# SCH_GP40_keyboard.net
KiCad netlist of a schematic drawn in EasyEDA
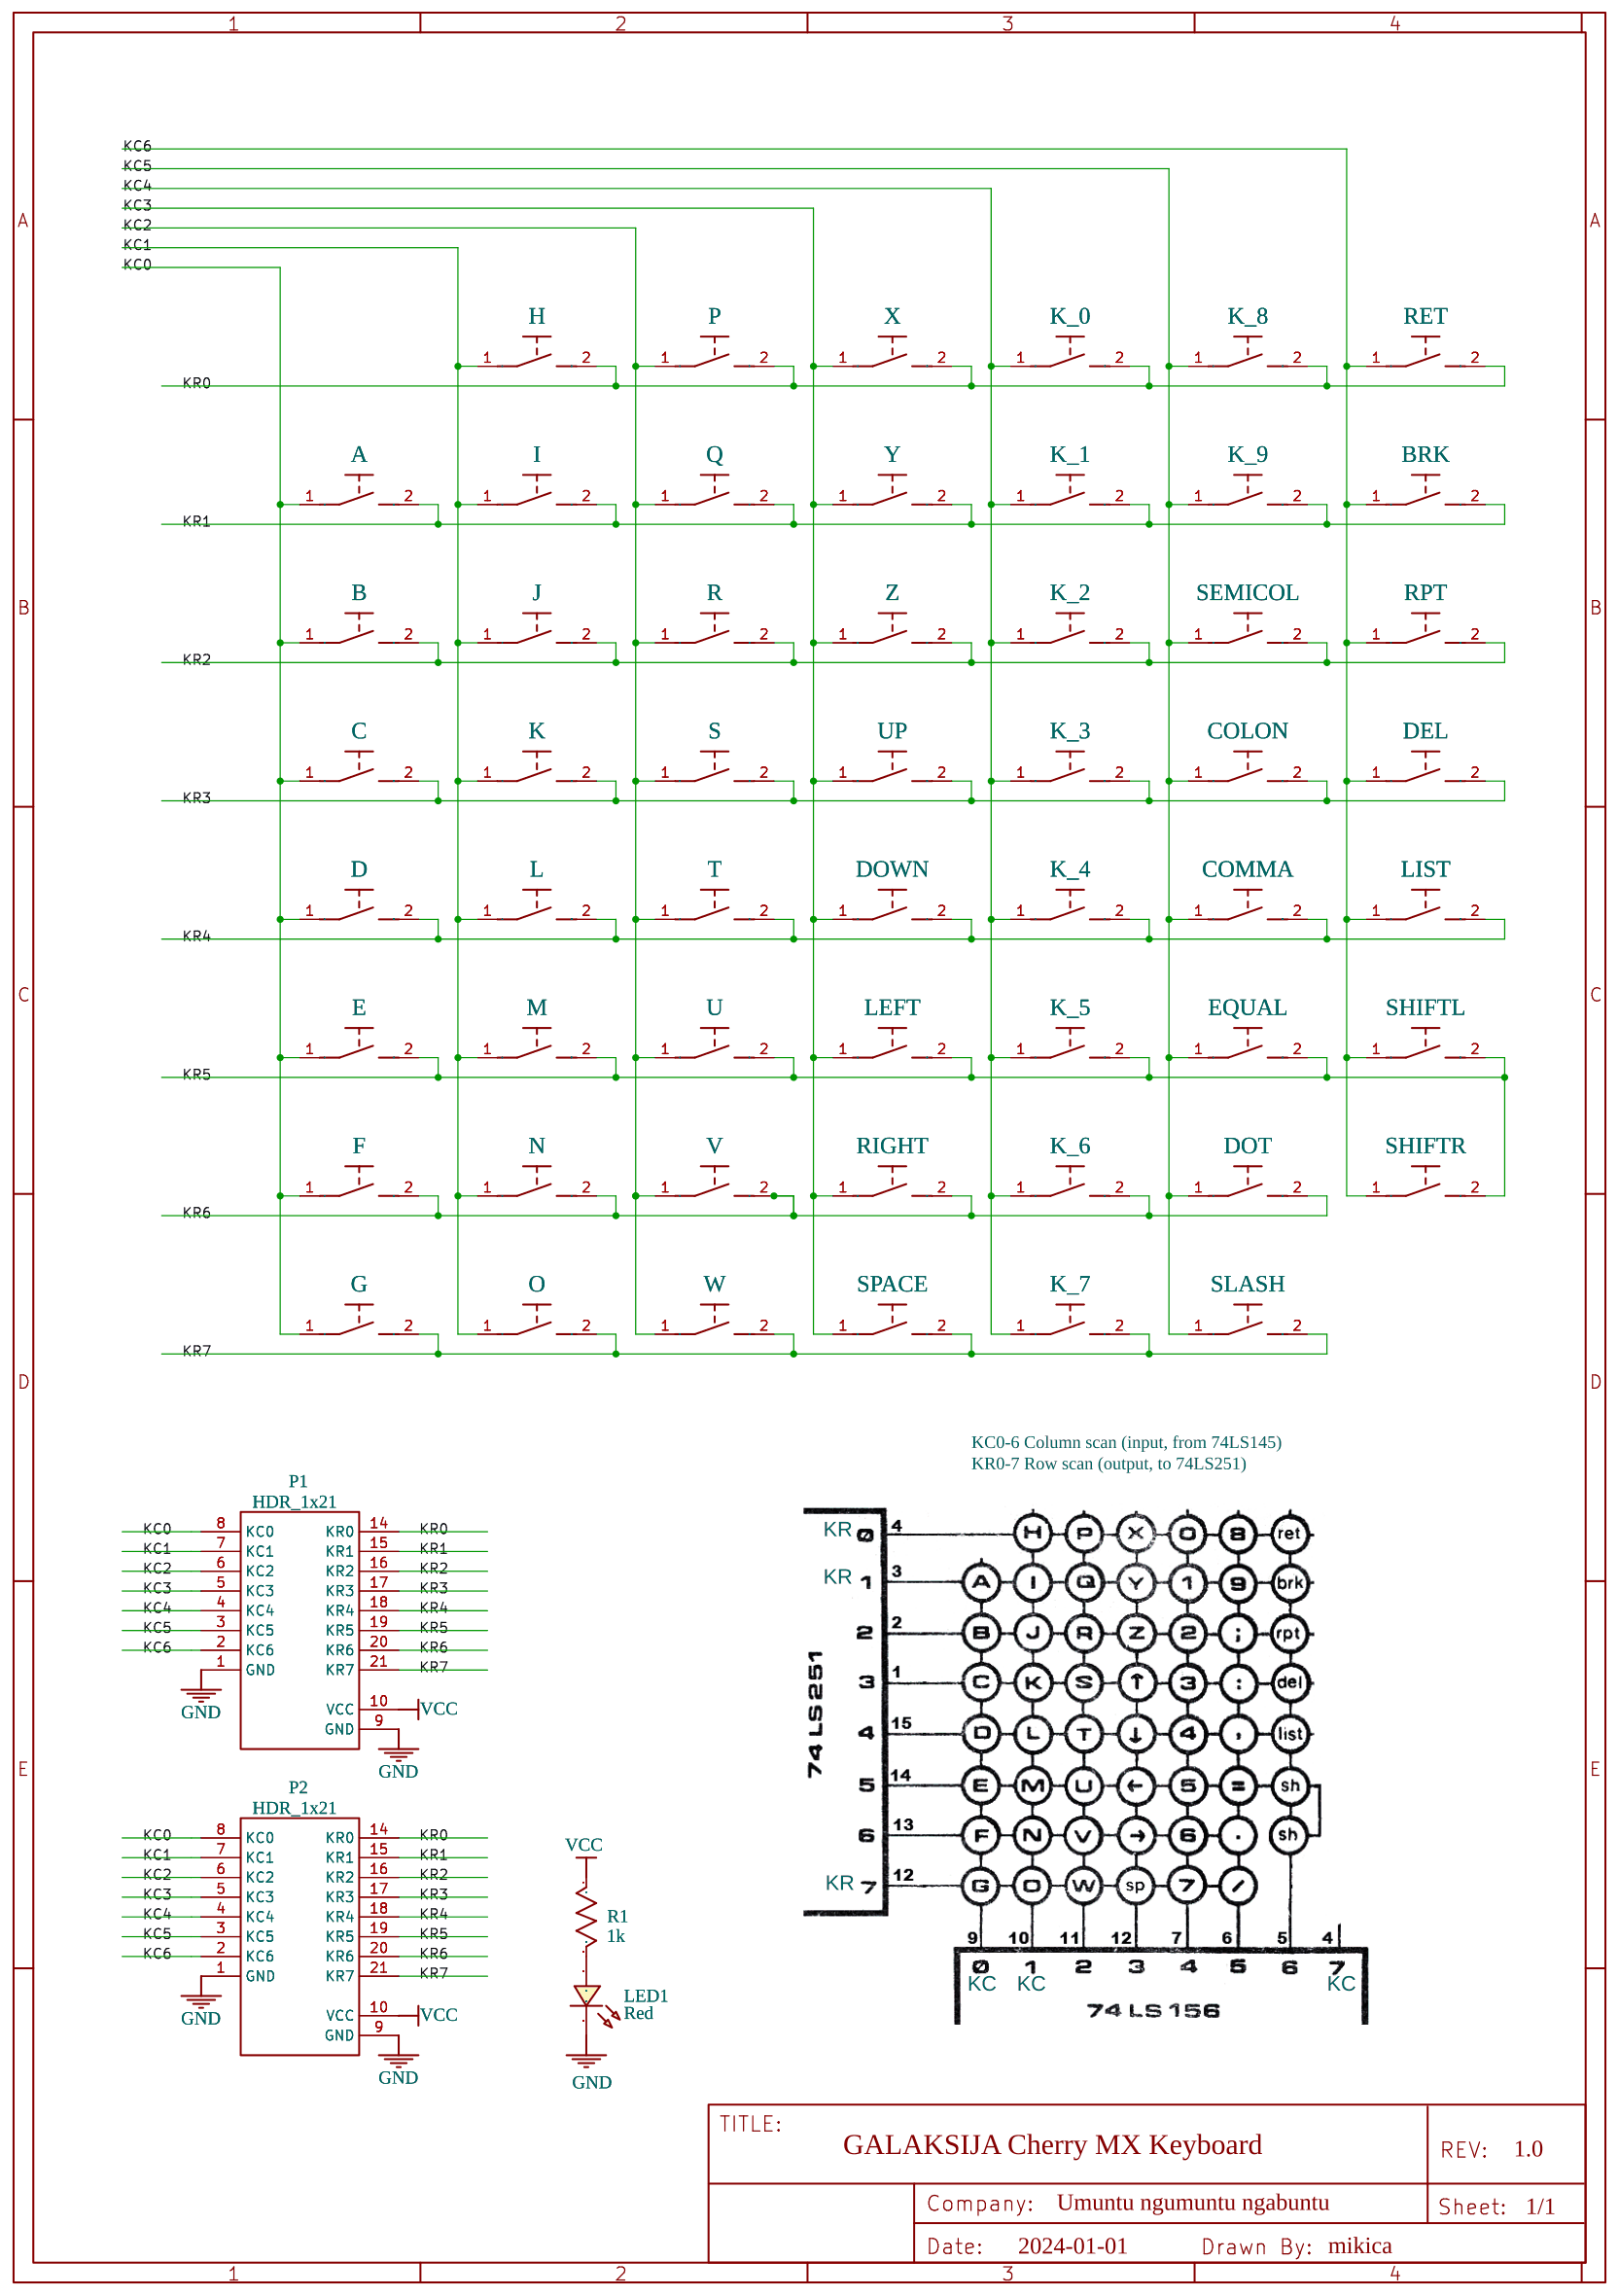
[diagram p0: schematic sheet]

(export (version "E")
  (design (tool "Eeschema 10.0.6"))
  (components
    (comp (ref "A")
      (value "CPG151101S21")
      (fields (field (name "Manufacturer") "Kailh(凯华)"))
      (libsource (lib "") (part "CPG151101S21_30"))
    )
    (comp (ref "B")
      (value "CPG151101S21")
      (fields (field (name "Manufacturer") "Kailh(凯华)"))
      (libsource (lib "") (part "CPG151101S21_25"))
    )
    (comp (ref "BRK")
      (value "CPG151101S21")
      (fields (field (name "Manufacturer") "Kailh(凯华)"))
      (libsource (lib "") (part "CPG151101S21_18"))
    )
    (comp (ref "C")
      (value "CPG151101S21")
      (fields (field (name "Manufacturer") "Kailh(凯华)"))
      (libsource (lib "") (part "CPG151101S21_35"))
    )
    (comp (ref "COLON")
      (value "CPG151101S21")
      (fields (field (name "Manufacturer") "Kailh(凯华)"))
      (libsource (lib "") (part "CPG151101S21_43"))
    )
    (comp (ref "COMMA")
      (value "CPG151101S21")
      (fields (field (name "Manufacturer") "Kailh(凯华)"))
      (libsource (lib "") (part "CPG151101S21_11"))
    )
    (comp (ref "D")
      (value "CPG151101S21")
      (fields (field (name "Manufacturer") "Kailh(凯华)"))
      (libsource (lib "") (part "CPG151101S21_33"))
    )
    (comp (ref "DEL")
      (value "CPG151101S21")
      (fields (field (name "Manufacturer") "Kailh(凯华)"))
      (libsource (lib "") (part "CPG151101S21_3"))
    )
    (comp (ref "DOT")
      (value "CPG151101S21")
      (fields (field (name "Manufacturer") "Kailh(凯华)"))
      (libsource (lib "") (part "CPG151101S21_26"))
    )
    (comp (ref "DOWN")
      (value "CPG151101S21")
      (fields (field (name "Manufacturer") "Kailh(凯华)"))
      (libsource (lib "") (part "CPG151101S21_9"))
    )
    (comp (ref "E")
      (value "CPG151101S21")
      (fields (field (name "Manufacturer") "Kailh(凯华)"))
      (libsource (lib "") (part "CPG151101S21_44"))
    )
    (comp (ref "EQUAL")
      (value "CPG151101S21")
      (fields (field (name "Manufacturer") "Kailh(凯华)"))
      (libsource (lib "") (part "CPG151101S21_27"))
    )
    (comp (ref "F")
      (value "CPG151101S21")
      (fields (field (name "Manufacturer") "Kailh(凯华)"))
      (libsource (lib "") (part "CPG151101S21_41"))
    )
    (comp (ref "G")
      (value "CPG151101S21")
      (fields (field (name "Manufacturer") "Kailh(凯华)"))
      (libsource (lib "") (part "CPG151101S21_37"))
    )
    (comp (ref "H")
      (value "CPG151101S21")
      (fields (field (name "Manufacturer") "Kailh(凯华)"))
      (libsource (lib "") (part "CPG151101S21_14"))
    )
    (comp (ref "I")
      (value "CPG151101S21")
      (fields (field (name "Manufacturer") "Kailh(凯华)"))
      (libsource (lib "") (part "CPG151101S21_32"))
    )
    (comp (ref "J")
      (value "CPG151101S21")
      (fields (field (name "Manufacturer") "Kailh(凯华)"))
      (libsource (lib "") (part "CPG151101S21_42"))
    )
    (comp (ref "K")
      (value "CPG151101S21")
      (fields (field (name "Manufacturer") "Kailh(凯华)"))
      (libsource (lib "") (part "CPG151101S21_10"))
    )
    (comp (ref "K_0")
      (value "CPG151101S21")
      (fields (field (name "Manufacturer") "Kailh(凯华)"))
      (libsource (lib "") (part "CPG151101S21_5"))
    )
    (comp (ref "K_1")
      (value "CPG151101S21")
      (fields (field (name "Manufacturer") "Kailh(凯华)"))
      (libsource (lib "") (part "CPG151101S21_5"))
    )
    (comp (ref "K_2")
      (value "CPG151101S21")
      (fields (field (name "Manufacturer") "Kailh(凯华)"))
      (libsource (lib "") (part "CPG151101S21_5"))
    )
    (comp (ref "K_3")
      (value "CPG151101S21")
      (fields (field (name "Manufacturer") "Kailh(凯华)"))
      (libsource (lib "") (part "CPG151101S21_5"))
    )
    (comp (ref "K_4")
      (value "CPG151101S21")
      (fields (field (name "Manufacturer") "Kailh(凯华)"))
      (libsource (lib "") (part "CPG151101S21_5"))
    )
    (comp (ref "K_5")
      (value "CPG151101S21")
      (fields (field (name "Manufacturer") "Kailh(凯华)"))
      (libsource (lib "") (part "CPG151101S21_5"))
    )
    (comp (ref "K_6")
      (value "CPG151101S21")
      (fields (field (name "Manufacturer") "Kailh(凯华)"))
      (libsource (lib "") (part "CPG151101S21_5"))
    )
    (comp (ref "K_7")
      (value "CPG151101S21")
      (fields (field (name "Manufacturer") "Kailh(凯华)"))
      (libsource (lib "") (part "CPG151101S21_5"))
    )
    (comp (ref "K_8")
      (value "CPG151101S21")
      (fields (field (name "Manufacturer") "Kailh(凯华)"))
      (libsource (lib "") (part "CPG151101S21_5"))
    )
    (comp (ref "K_9")
      (value "CPG151101S21")
      (fields (field (name "Manufacturer") "Kailh(凯华)"))
      (libsource (lib "") (part "CPG151101S21_5"))
    )
    (comp (ref "L")
      (value "CPG151101S21")
      (fields (field (name "Manufacturer") "Kailh(凯华)"))
      (libsource (lib "") (part "CPG151101S21_24"))
    )
    (comp (ref "LED1")
      (value "Red")
      (fields
        (field (name "Manufacturer Part") "204-10SDRD/S530-A3-L")
        (field (name "Manufacturer") "EVERLIGHT(台湾亿光)")
      )
      (libsource (lib "") (part "LED-TH-3mm_R"))
    )
    (comp (ref "LEFT")
      (value "CPG151101S21")
      (fields (field (name "Manufacturer") "Kailh(凯华)"))
      (libsource (lib "") (part "CPG151101S21_4"))
    )
    (comp (ref "LIST")
      (value "CPG151101S21")
      (fields (field (name "Manufacturer") "Kailh(凯华)"))
      (libsource (lib "") (part "CPG151101S21_2"))
    )
    (comp (ref "M")
      (value "CPG151101S21")
      (fields (field (name "Manufacturer") "Kailh(凯华)"))
      (libsource (lib "") (part "CPG151101S21_19"))
    )
    (comp (ref "N")
      (value "CPG151101S21")
      (fields (field (name "Manufacturer") "Kailh(凯华)"))
      (libsource (lib "") (part "CPG151101S21_15"))
    )
    (comp (ref "O")
      (value "CPG151101S21")
      (fields (field (name "Manufacturer") "Kailh(凯华)"))
      (libsource (lib "") (part "CPG151101S21_29"))
    )
    (comp (ref "P")
      (value "CPG151101S21")
      (fields (field (name "Manufacturer") "Kailh(凯华)"))
      (libsource (lib "") (part "CPG151101S21_16"))
    )
    (comp (ref "P1") (value "HDR_1x21") (libsource (lib "") (part "GP40_KBD")))
    (comp (ref "P2") (value "HDR_1x21") (libsource (lib "") (part "GP40_KBD")))
    (comp (ref "Q")
      (value "CPG151101S21")
      (fields (field (name "Manufacturer") "Kailh(凯华)"))
      (libsource (lib "") (part "CPG151101S21_8"))
    )
    (comp (ref "R")
      (value "CPG151101S21")
      (fields (field (name "Manufacturer") "Kailh(凯华)"))
      (libsource (lib "") (part "CPG151101S21_21"))
    )
    (comp (ref "R1") (value "1k") (libsource (lib "") (part "R_0805_US")))
    (comp (ref "RET")
      (value "CPG151101S21")
      (fields (field (name "Manufacturer") "Kailh(凯华)"))
      (libsource (lib "") (part "CPG151101S21_17"))
    )
    (comp (ref "RIGHT")
      (value "CPG151101S21")
      (fields (field (name "Manufacturer") "Kailh(凯华)"))
      (libsource (lib "") (part "CPG151101S21_6"))
    )
    (comp (ref "RPT")
      (value "CPG151101S21")
      (fields (field (name "Manufacturer") "Kailh(凯华)"))
      (libsource (lib "") (part "CPG151101S21_13"))
    )
    (comp (ref "S")
      (value "CPG151101S21")
      (fields (field (name "Manufacturer") "Kailh(凯华)"))
      (libsource (lib "") (part "CPG151101S21_34"))
    )
    (comp (ref "SEMICOL")
      (value "CPG151101S21")
      (fields (field (name "Manufacturer") "Kailh(凯华)"))
      (libsource (lib "") (part "CPG151101S21_31"))
    )
    (comp (ref "SHIFTL")
      (value "CPG151101S21")
      (fields (field (name "Manufacturer") "Kailh(凯华)"))
      (libsource (lib "") (part "CPG151101S21_1"))
    )
    (comp (ref "SHIFTR")
      (value "CPG151101S21")
      (fields (field (name "Manufacturer") "Kailh(凯华)"))
      (libsource (lib "") (part "CPG151101S21_38"))
    )
    (comp (ref "SLASH")
      (value "CPG151101S21")
      (fields (field (name "Manufacturer") "Kailh(凯华)"))
      (libsource (lib "") (part "CPG151101S21"))
    )
    (comp (ref "SPACE")
      (value "CPG151101S21")
      (fields (field (name "Manufacturer") "Kailh(凯华)"))
      (libsource (lib "") (part "CPG151101S21_36"))
    )
    (comp (ref "T")
      (value "CPG151101S21")
      (fields (field (name "Manufacturer") "Kailh(凯华)"))
      (libsource (lib "") (part "CPG151101S21_7"))
    )
    (comp (ref "U")
      (value "CPG151101S21")
      (fields (field (name "Manufacturer") "Kailh(凯华)"))
      (libsource (lib "") (part "CPG151101S21_12"))
    )
    (comp (ref "UP")
      (value "CPG151101S21")
      (fields (field (name "Manufacturer") "Kailh(凯华)"))
      (libsource (lib "") (part "CPG151101S21_40"))
    )
    (comp (ref "V")
      (value "CPG151101S21")
      (fields (field (name "Manufacturer") "Kailh(凯华)"))
      (libsource (lib "") (part "CPG151101S21_22"))
    )
    (comp (ref "W")
      (value "CPG151101S21")
      (fields (field (name "Manufacturer") "Kailh(凯华)"))
      (libsource (lib "") (part "CPG151101S21_20"))
    )
    (comp (ref "X")
      (value "CPG151101S21")
      (fields (field (name "Manufacturer") "Kailh(凯华)"))
      (libsource (lib "") (part "CPG151101S21_28"))
    )
    (comp (ref "Y")
      (value "CPG151101S21")
      (fields (field (name "Manufacturer") "Kailh(凯华)"))
      (libsource (lib "") (part "CPG151101S21_23"))
    )
    (comp (ref "Z")
      (value "CPG151101S21")
      (fields (field (name "Manufacturer") "Kailh(凯华)"))
      (libsource (lib "") (part "CPG151101S21_39"))
    )
  )
  (nets
    (net (code "1") (name "/KC0") (class "Default")
      (node (ref "A") (pin "1") (pinfunction "1_1") (pintype "unspecified"))
      (node (ref "B") (pin "1") (pinfunction "1_1") (pintype "unspecified"))
      (node (ref "C") (pin "1") (pinfunction "1_1") (pintype "unspecified"))
      (node (ref "D") (pin "1") (pinfunction "1_1") (pintype "unspecified"))
      (node (ref "E") (pin "1") (pinfunction "1_1") (pintype "unspecified"))
      (node (ref "F") (pin "1") (pinfunction "1_1") (pintype "unspecified"))
      (node (ref "G") (pin "1") (pinfunction "1_1") (pintype "unspecified"))
      (node (ref "P1") (pin "8") (pinfunction "KC0_8") (pintype "unspecified"))
      (node (ref "P2") (pin "8") (pinfunction "KC0_8") (pintype "unspecified"))
    )
    (net (code "2") (name "/KC1") (class "Default")
      (node (ref "H") (pin "1") (pinfunction "1_1") (pintype "unspecified"))
      (node (ref "I") (pin "1") (pinfunction "1_1") (pintype "unspecified"))
      (node (ref "J") (pin "1") (pinfunction "1_1") (pintype "unspecified"))
      (node (ref "K") (pin "1") (pinfunction "1_1") (pintype "unspecified"))
      (node (ref "L") (pin "1") (pinfunction "1_1") (pintype "unspecified"))
      (node (ref "M") (pin "1") (pinfunction "1_1") (pintype "unspecified"))
      (node (ref "N") (pin "1") (pinfunction "1_1") (pintype "unspecified"))
      (node (ref "O") (pin "1") (pinfunction "1_1") (pintype "unspecified"))
      (node (ref "P1") (pin "7") (pinfunction "KC1_7") (pintype "unspecified"))
      (node (ref "P2") (pin "7") (pinfunction "KC1_7") (pintype "unspecified"))
    )
    (net (code "3") (name "/KC2") (class "Default")
      (node (ref "P") (pin "1") (pinfunction "1_1") (pintype "unspecified"))
      (node (ref "P1") (pin "6") (pinfunction "KC2_6") (pintype "unspecified"))
      (node (ref "P2") (pin "6") (pinfunction "KC2_6") (pintype "unspecified"))
      (node (ref "Q") (pin "1") (pinfunction "1_1") (pintype "unspecified"))
      (node (ref "R") (pin "1") (pinfunction "1_1") (pintype "unspecified"))
      (node (ref "S") (pin "1") (pinfunction "1_1") (pintype "unspecified"))
      (node (ref "T") (pin "1") (pinfunction "1_1") (pintype "unspecified"))
      (node (ref "U") (pin "1") (pinfunction "1_1") (pintype "unspecified"))
      (node (ref "V") (pin "1") (pinfunction "1_1") (pintype "unspecified"))
      (node (ref "W") (pin "1") (pinfunction "1_1") (pintype "unspecified"))
    )
    (net (code "4") (name "/KC3") (class "Default")
      (node (ref "DOWN") (pin "1") (pinfunction "1_1") (pintype "unspecified"))
      (node (ref "LEFT") (pin "1") (pinfunction "1_1") (pintype "unspecified"))
      (node (ref "P1") (pin "5") (pinfunction "KC3_5") (pintype "unspecified"))
      (node (ref "P2") (pin "5") (pinfunction "KC3_5") (pintype "unspecified"))
      (node (ref "RIGHT") (pin "1") (pinfunction "1_1") (pintype "unspecified"))
      (node (ref "SPACE") (pin "1") (pinfunction "1_1") (pintype "unspecified"))
      (node (ref "UP") (pin "1") (pinfunction "1_1") (pintype "unspecified"))
      (node (ref "X") (pin "1") (pinfunction "1_1") (pintype "unspecified"))
      (node (ref "Y") (pin "1") (pinfunction "1_1") (pintype "unspecified"))
      (node (ref "Z") (pin "1") (pinfunction "1_1") (pintype "unspecified"))
    )
    (net (code "5") (name "/KC4") (class "Default")
      (node (ref "K_0") (pin "1") (pinfunction "1_1") (pintype "unspecified"))
      (node (ref "K_1") (pin "1") (pinfunction "1_1") (pintype "unspecified"))
      (node (ref "K_2") (pin "1") (pinfunction "1_1") (pintype "unspecified"))
      (node (ref "K_3") (pin "1") (pinfunction "1_1") (pintype "unspecified"))
      (node (ref "K_4") (pin "1") (pinfunction "1_1") (pintype "unspecified"))
      (node (ref "K_5") (pin "1") (pinfunction "1_1") (pintype "unspecified"))
      (node (ref "K_6") (pin "1") (pinfunction "1_1") (pintype "unspecified"))
      (node (ref "K_7") (pin "1") (pinfunction "1_1") (pintype "unspecified"))
      (node (ref "P1") (pin "4") (pinfunction "KC4_4") (pintype "unspecified"))
      (node (ref "P2") (pin "4") (pinfunction "KC4_4") (pintype "unspecified"))
    )
    (net (code "6") (name "/KC5") (class "Default")
      (node (ref "COLON") (pin "1") (pinfunction "1_1") (pintype "unspecified"))
      (node (ref "COMMA") (pin "1") (pinfunction "1_1") (pintype "unspecified"))
      (node (ref "DOT") (pin "1") (pinfunction "1_1") (pintype "unspecified"))
      (node (ref "EQUAL") (pin "1") (pinfunction "1_1") (pintype "unspecified"))
      (node (ref "K_8") (pin "1") (pinfunction "1_1") (pintype "unspecified"))
      (node (ref "K_9") (pin "1") (pinfunction "1_1") (pintype "unspecified"))
      (node (ref "P1") (pin "3") (pinfunction "KC5_3") (pintype "unspecified"))
      (node (ref "P2") (pin "3") (pinfunction "KC5_3") (pintype "unspecified"))
      (node (ref "SEMICOL") (pin "1") (pinfunction "1_1") (pintype "unspecified"))
      (node (ref "SLASH") (pin "1") (pinfunction "1_1") (pintype "unspecified"))
    )
    (net (code "7") (name "/KC6") (class "Default")
      (node (ref "BRK") (pin "1") (pinfunction "1_1") (pintype "unspecified"))
      (node (ref "DEL") (pin "1") (pinfunction "1_1") (pintype "unspecified"))
      (node (ref "LIST") (pin "1") (pinfunction "1_1") (pintype "unspecified"))
      (node (ref "P1") (pin "2") (pinfunction "KC6_2") (pintype "unspecified"))
      (node (ref "P2") (pin "2") (pinfunction "KC6_2") (pintype "unspecified"))
      (node (ref "RET") (pin "1") (pinfunction "1_1") (pintype "unspecified"))
      (node (ref "RPT") (pin "1") (pinfunction "1_1") (pintype "unspecified"))
      (node (ref "SHIFTL") (pin "1") (pinfunction "1_1") (pintype "unspecified"))
      (node (ref "SHIFTR") (pin "1") (pinfunction "1_1") (pintype "unspecified"))
    )
    (net (code "8") (name "/KR0") (class "Default")
      (node (ref "H") (pin "2") (pinfunction "2_2") (pintype "unspecified"))
      (node (ref "K_0") (pin "2") (pinfunction "2_2") (pintype "unspecified"))
      (node (ref "K_8") (pin "2") (pinfunction "2_2") (pintype "unspecified"))
      (node (ref "P") (pin "2") (pinfunction "2_2") (pintype "unspecified"))
      (node (ref "P1") (pin "14") (pinfunction "KR0_14") (pintype "unspecified"))
      (node (ref "P2") (pin "14") (pinfunction "KR0_14") (pintype "unspecified"))
      (node (ref "RET") (pin "2") (pinfunction "2_2") (pintype "unspecified"))
      (node (ref "X") (pin "2") (pinfunction "2_2") (pintype "unspecified"))
    )
    (net (code "9") (name "/KR1") (class "Default")
      (node (ref "A") (pin "2") (pinfunction "2_2") (pintype "unspecified"))
      (node (ref "BRK") (pin "2") (pinfunction "2_2") (pintype "unspecified"))
      (node (ref "I") (pin "2") (pinfunction "2_2") (pintype "unspecified"))
      (node (ref "K_1") (pin "2") (pinfunction "2_2") (pintype "unspecified"))
      (node (ref "K_9") (pin "2") (pinfunction "2_2") (pintype "unspecified"))
      (node (ref "P1") (pin "15") (pinfunction "KR1_15") (pintype "unspecified"))
      (node (ref "P2") (pin "15") (pinfunction "KR1_15") (pintype "unspecified"))
      (node (ref "Q") (pin "2") (pinfunction "2_2") (pintype "unspecified"))
      (node (ref "Y") (pin "2") (pinfunction "2_2") (pintype "unspecified"))
    )
    (net (code "10") (name "/KR2") (class "Default")
      (node (ref "B") (pin "2") (pinfunction "2_2") (pintype "unspecified"))
      (node (ref "J") (pin "2") (pinfunction "2_2") (pintype "unspecified"))
      (node (ref "K_2") (pin "2") (pinfunction "2_2") (pintype "unspecified"))
      (node (ref "P1") (pin "16") (pinfunction "KR2_16") (pintype "unspecified"))
      (node (ref "P2") (pin "16") (pinfunction "KR2_16") (pintype "unspecified"))
      (node (ref "R") (pin "2") (pinfunction "2_2") (pintype "unspecified"))
      (node (ref "RPT") (pin "2") (pinfunction "2_2") (pintype "unspecified"))
      (node (ref "SEMICOL") (pin "2") (pinfunction "2_2") (pintype "unspecified"))
      (node (ref "Z") (pin "2") (pinfunction "2_2") (pintype "unspecified"))
    )
    (net (code "11") (name "/KR3") (class "Default")
      (node (ref "C") (pin "2") (pinfunction "2_2") (pintype "unspecified"))
      (node (ref "COLON") (pin "2") (pinfunction "2_2") (pintype "unspecified"))
      (node (ref "DEL") (pin "2") (pinfunction "2_2") (pintype "unspecified"))
      (node (ref "K") (pin "2") (pinfunction "2_2") (pintype "unspecified"))
      (node (ref "K_3") (pin "2") (pinfunction "2_2") (pintype "unspecified"))
      (node (ref "P1") (pin "17") (pinfunction "KR3_17") (pintype "unspecified"))
      (node (ref "P2") (pin "17") (pinfunction "KR3_17") (pintype "unspecified"))
      (node (ref "S") (pin "2") (pinfunction "2_2") (pintype "unspecified"))
      (node (ref "UP") (pin "2") (pinfunction "2_2") (pintype "unspecified"))
    )
    (net (code "12") (name "/KR4") (class "Default")
      (node (ref "COMMA") (pin "2") (pinfunction "2_2") (pintype "unspecified"))
      (node (ref "D") (pin "2") (pinfunction "2_2") (pintype "unspecified"))
      (node (ref "DOWN") (pin "2") (pinfunction "2_2") (pintype "unspecified"))
      (node (ref "K_4") (pin "2") (pinfunction "2_2") (pintype "unspecified"))
      (node (ref "L") (pin "2") (pinfunction "2_2") (pintype "unspecified"))
      (node (ref "LIST") (pin "2") (pinfunction "2_2") (pintype "unspecified"))
      (node (ref "P1") (pin "18") (pinfunction "KR4_18") (pintype "unspecified"))
      (node (ref "P2") (pin "18") (pinfunction "KR4_18") (pintype "unspecified"))
      (node (ref "T") (pin "2") (pinfunction "2_2") (pintype "unspecified"))
    )
    (net (code "13") (name "/KR5") (class "Default")
      (node (ref "E") (pin "2") (pinfunction "2_2") (pintype "unspecified"))
      (node (ref "EQUAL") (pin "2") (pinfunction "2_2") (pintype "unspecified"))
      (node (ref "K_5") (pin "2") (pinfunction "2_2") (pintype "unspecified"))
      (node (ref "LEFT") (pin "2") (pinfunction "2_2") (pintype "unspecified"))
      (node (ref "M") (pin "2") (pinfunction "2_2") (pintype "unspecified"))
      (node (ref "P1") (pin "19") (pinfunction "KR5_19") (pintype "unspecified"))
      (node (ref "P2") (pin "19") (pinfunction "KR5_19") (pintype "unspecified"))
      (node (ref "SHIFTL") (pin "2") (pinfunction "2_2") (pintype "unspecified"))
      (node (ref "SHIFTR") (pin "2") (pinfunction "2_2") (pintype "unspecified"))
      (node (ref "U") (pin "2") (pinfunction "2_2") (pintype "unspecified"))
    )
    (net (code "14") (name "/KR6") (class "Default")
      (node (ref "DOT") (pin "2") (pinfunction "2_2") (pintype "unspecified"))
      (node (ref "F") (pin "2") (pinfunction "2_2") (pintype "unspecified"))
      (node (ref "K_6") (pin "2") (pinfunction "2_2") (pintype "unspecified"))
      (node (ref "N") (pin "2") (pinfunction "2_2") (pintype "unspecified"))
      (node (ref "P1") (pin "20") (pinfunction "KR6_20") (pintype "unspecified"))
      (node (ref "P2") (pin "20") (pinfunction "KR6_20") (pintype "unspecified"))
      (node (ref "RIGHT") (pin "2") (pinfunction "2_2") (pintype "unspecified"))
      (node (ref "V") (pin "2") (pinfunction "2_2") (pintype "unspecified"))
    )
    (net (code "15") (name "/KR7") (class "Default")
      (node (ref "G") (pin "2") (pinfunction "2_2") (pintype "unspecified"))
      (node (ref "K_7") (pin "2") (pinfunction "2_2") (pintype "unspecified"))
      (node (ref "O") (pin "2") (pinfunction "2_2") (pintype "unspecified"))
      (node (ref "P1") (pin "21") (pinfunction "KR7_21") (pintype "unspecified"))
      (node (ref "P2") (pin "21") (pinfunction "KR7_21") (pintype "unspecified"))
      (node (ref "SLASH") (pin "2") (pinfunction "2_2") (pintype "unspecified"))
      (node (ref "SPACE") (pin "2") (pinfunction "2_2") (pintype "unspecified"))
      (node (ref "W") (pin "2") (pinfunction "2_2") (pintype "unspecified"))
    )
    (net (code "16") (name "GND") (class "Default")
      (node (ref "LED1") (pin "2") (pinfunction "2_2") (pintype "unspecified"))
      (node (ref "P1") (pin "1") (pinfunction "GND_1") (pintype "unspecified"))
      (node (ref "P1") (pin "9") (pinfunction "GND_9") (pintype "unspecified"))
      (node (ref "P2") (pin "1") (pinfunction "GND_1") (pintype "unspecified"))
      (node (ref "P2") (pin "9") (pinfunction "GND_9") (pintype "unspecified"))
    )
    (net (code "17") (name "Net-(LED1-Pad1)") (class "Default")
      (node (ref "LED1") (pin "1") (pinfunction "1_1") (pintype "unspecified"))
      (node (ref "R1") (pin "2") (pinfunction "2_2") (pintype "unspecified"))
    )
    (net (code "18") (name "VCC") (class "Default")
      (node (ref "P1") (pin "10") (pinfunction "VCC_10") (pintype "unspecified"))
      (node (ref "P2") (pin "10") (pinfunction "VCC_10") (pintype "unspecified"))
      (node (ref "R1") (pin "1") (pinfunction "1_1") (pintype "unspecified"))
    )
  )
)
